# UART_TypeC.net
KiCad netlist of a schematic drawn in Altium Designer
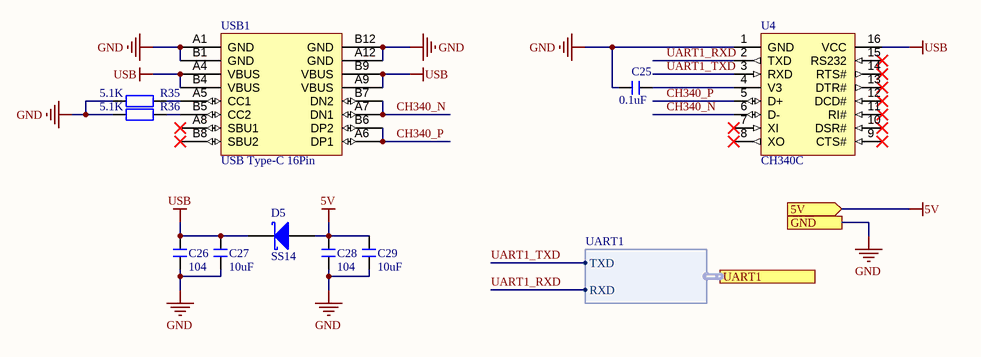
[diagram p0: UART_TypeC.SchDoc]

(export (version "E")
  (design (tool "Eeschema 10.0.6"))
  (components
    (comp (ref "C25")
      (value "0.1uF")
      (footprint "C 0603_L")
      (description "贴片电容")
      (libsource (lib "0.1 - 电阻-电容-电感") (part "C"))
    )
    (comp (ref "C26")
      (value "104")
      (footprint "C 0603_L")
      (description "贴片电容")
      (libsource (lib "0.1 - 电阻-电容-电感") (part "C"))
    )
    (comp (ref "C27")
      (value "10uF")
      (footprint "C 0603_L")
      (description "贴片电容")
      (libsource (lib "0.1 - 电阻-电容-电感") (part "C"))
    )
    (comp (ref "C28")
      (value "104")
      (footprint "C 0603_L")
      (description "贴片电容")
      (libsource (lib "0.1 - 电阻-电容-电感") (part "C"))
    )
    (comp (ref "C29")
      (value "10uF")
      (footprint "C 0603_L")
      (description "贴片电容")
      (libsource (lib "0.1 - 电阻-电容-电感") (part "C"))
    )
    (comp (ref "D5")
      (value "SS14")
      (footprint "SMA")
      (description "肖特基二极管")
      (libsource (lib "0.2 - 二极管-整流桥") (part "SS14"))
    )
    (comp (ref "R35")
      (value "5.1K")
      (footprint "R 0603_L")
      (description "贴片电阻")
      (fields (field (name "版权归属") "来自淘宝 ID：黄晶宝石"))
      (libsource (lib "0.1 - 电阻-电容-电感") (part "R"))
    )
    (comp (ref "R36")
      (value "5.1K")
      (footprint "R 0603_L")
      (description "贴片电阻")
      (fields (field (name "版权归属") "来自淘宝 ID：黄晶宝石"))
      (libsource (lib "0.1 - 电阻-电容-电感") (part "R"))
    )
    (comp (ref "U4")
      (value "CH340C")
      (footprint "SOP16_L")
      (description "串口转USB")
      (fields (field (name "版权归属") "封装库来自淘宝 ID：黄晶宝石"))
      (libsource (lib "1.0 - 常见芯片") (part "CH340G"))
    )
    (comp (ref "USB1")
      (value "USB Type-C 16Pin")
      (footprint "USB-C-SMD-TAILOR")
      (libsource (lib "0.8 - 以太网-音频-USB插座") (part "USB Type-C 16Pin"))
    )
  )
  (nets
    (net (code "2") (name "/CH340_N") (class "Default")
      (node (ref "U4") (pin "6") (pinfunction "D-_6") (pintype "bidirectional"))
      (node (ref "USB1") (pin "A7") (pinfunction "DN1_A7") (pintype "bidirectional"))
      (node (ref "USB1") (pin "B7") (pinfunction "DN2_B7") (pintype "bidirectional"))
    )
    (net (code "3") (name "/CH340_P") (class "Default")
      (node (ref "U4") (pin "5") (pinfunction "D+_5") (pintype "bidirectional"))
      (node (ref "USB1") (pin "A6") (pinfunction "DP1_A6") (pintype "bidirectional"))
      (node (ref "USB1") (pin "B6") (pinfunction "DP2_B6") (pintype "bidirectional"))
    )
    (net (code "4") (name "/UART1_RXD") (class "Default")
      (node (ref "U4") (pin "2") (pinfunction "TXD_2") (pintype "output"))
    )
    (net (code "5") (name "/UART1_TXD") (class "Default")
      (node (ref "U4") (pin "3") (pinfunction "RXD_3") (pintype "input"))
    )
    (net (code "7") (name "5V") (class "Default")
      (node (ref "C28") (pin "2") (pinfunction "2_2") (pintype "passive"))
      (node (ref "C29") (pin "2") (pinfunction "2_2") (pintype "passive"))
      (node (ref "D5") (pin "1") (pinfunction "A_1") (pintype "passive"))
    )
    (net (code "8") (name "GND") (class "Default")
      (node (ref "C25") (pin "1") (pinfunction "1_1") (pintype "passive"))
      (node (ref "C26") (pin "1") (pinfunction "1_1") (pintype "passive"))
      (node (ref "C27") (pin "1") (pinfunction "1_1") (pintype "passive"))
      (node (ref "C28") (pin "1") (pinfunction "1_1") (pintype "passive"))
      (node (ref "C29") (pin "1") (pinfunction "1_1") (pintype "passive"))
      (node (ref "R35") (pin "1") (pinfunction "1_1") (pintype "passive"))
      (node (ref "R36") (pin "1") (pinfunction "1_1") (pintype "passive"))
      (node (ref "U4") (pin "1") (pinfunction "GND_1") (pintype "power_in"))
      (node (ref "USB1") (pin "A1") (pinfunction "GND_A1") (pintype "power_in"))
      (node (ref "USB1") (pin "A12") (pinfunction "GND_A12") (pintype "power_in"))
      (node (ref "USB1") (pin "B1") (pinfunction "GND_B1") (pintype "power_in"))
      (node (ref "USB1") (pin "B12") (pinfunction "GND_B12") (pintype "power_in"))
    )
    (net (code "9") (name "Net-(U4-V3)") (class "Default")
      (node (ref "C25") (pin "2") (pinfunction "2_2") (pintype "passive"))
      (node (ref "U4") (pin "4") (pinfunction "V3_4") (pintype "power_in"))
    )
    (net (code "10") (name "Net-(USB1-CC1)") (class "Default")
      (node (ref "R35") (pin "2") (pinfunction "2_2") (pintype "passive"))
      (node (ref "USB1") (pin "A5") (pinfunction "CC1_A5") (pintype "bidirectional"))
    )
    (net (code "11") (name "Net-(USB1-CC2)") (class "Default")
      (node (ref "R36") (pin "2") (pinfunction "2_2") (pintype "passive"))
      (node (ref "USB1") (pin "B5") (pinfunction "CC2_B5") (pintype "bidirectional"))
    )
    (net (code "12") (name "USB") (class "Default")
      (node (ref "C26") (pin "2") (pinfunction "2_2") (pintype "passive"))
      (node (ref "C27") (pin "2") (pinfunction "2_2") (pintype "passive"))
      (node (ref "D5") (pin "2") (pinfunction "K_2") (pintype "passive"))
      (node (ref "U4") (pin "16") (pinfunction "VCC_16") (pintype "power_in"))
      (node (ref "USB1") (pin "A4") (pinfunction "VBUS_A4") (pintype "power_in"))
      (node (ref "USB1") (pin "A9") (pinfunction "VBUS_A9") (pintype "power_in"))
      (node (ref "USB1") (pin "B4") (pinfunction "VBUS_B4") (pintype "power_in"))
      (node (ref "USB1") (pin "B9") (pinfunction "VBUS_B9") (pintype "power_in"))
    )
    (net (code "13") (name "unconnected-(U4-CTS#-Pad9)") (class "Default")
      (node (ref "U4") (pin "9") (pinfunction "CTS#_9") (pintype "input+no_connect"))
    )
    (net (code "14") (name "unconnected-(U4-DCD#-Pad12)") (class "Default")
      (node (ref "U4") (pin "12") (pinfunction "DCD#_12") (pintype "input+no_connect"))
    )
    (net (code "15") (name "unconnected-(U4-DSR#-Pad10)") (class "Default")
      (node (ref "U4") (pin "10") (pinfunction "DSR#_10") (pintype "input+no_connect"))
    )
    (net (code "16") (name "unconnected-(U4-DTR#-Pad13)") (class "Default")
      (node (ref "U4") (pin "13") (pinfunction "DTR#_13") (pintype "output+no_connect"))
    )
    (net (code "17") (name "unconnected-(U4-RI#-Pad11)") (class "Default")
      (node (ref "U4") (pin "11") (pinfunction "RI#_11") (pintype "input+no_connect"))
    )
    (net (code "18") (name "unconnected-(U4-RS232-Pad15)") (class "Default")
      (node (ref "U4") (pin "15") (pinfunction "RS232_15") (pintype "input+no_connect"))
    )
    (net (code "19") (name "unconnected-(U4-RTS#-Pad14)") (class "Default")
      (node (ref "U4") (pin "14") (pinfunction "RTS#_14") (pintype "output+no_connect"))
    )
    (net (code "20") (name "unconnected-(U4-XI-Pad7)") (class "Default")
      (node (ref "U4") (pin "7") (pinfunction "XI_7") (pintype "input+no_connect"))
    )
    (net (code "21") (name "unconnected-(U4-XO-Pad8)") (class "Default")
      (node (ref "U4") (pin "8") (pinfunction "XO_8") (pintype "output+no_connect"))
    )
    (net (code "22") (name "unconnected-(USB1-SBU1-PadA8)") (class "Default")
      (node (ref "USB1") (pin "A8") (pinfunction "SBU1_A8") (pintype "bidirectional+no_connect"))
    )
    (net (code "23") (name "unconnected-(USB1-SBU2-PadB8)") (class "Default")
      (node (ref "USB1") (pin "B8") (pinfunction "SBU2_B8") (pintype "bidirectional+no_connect"))
    )
  )
)
